# sch_camera.net
KiCad netlist of a schematic drawn in Altium Designer
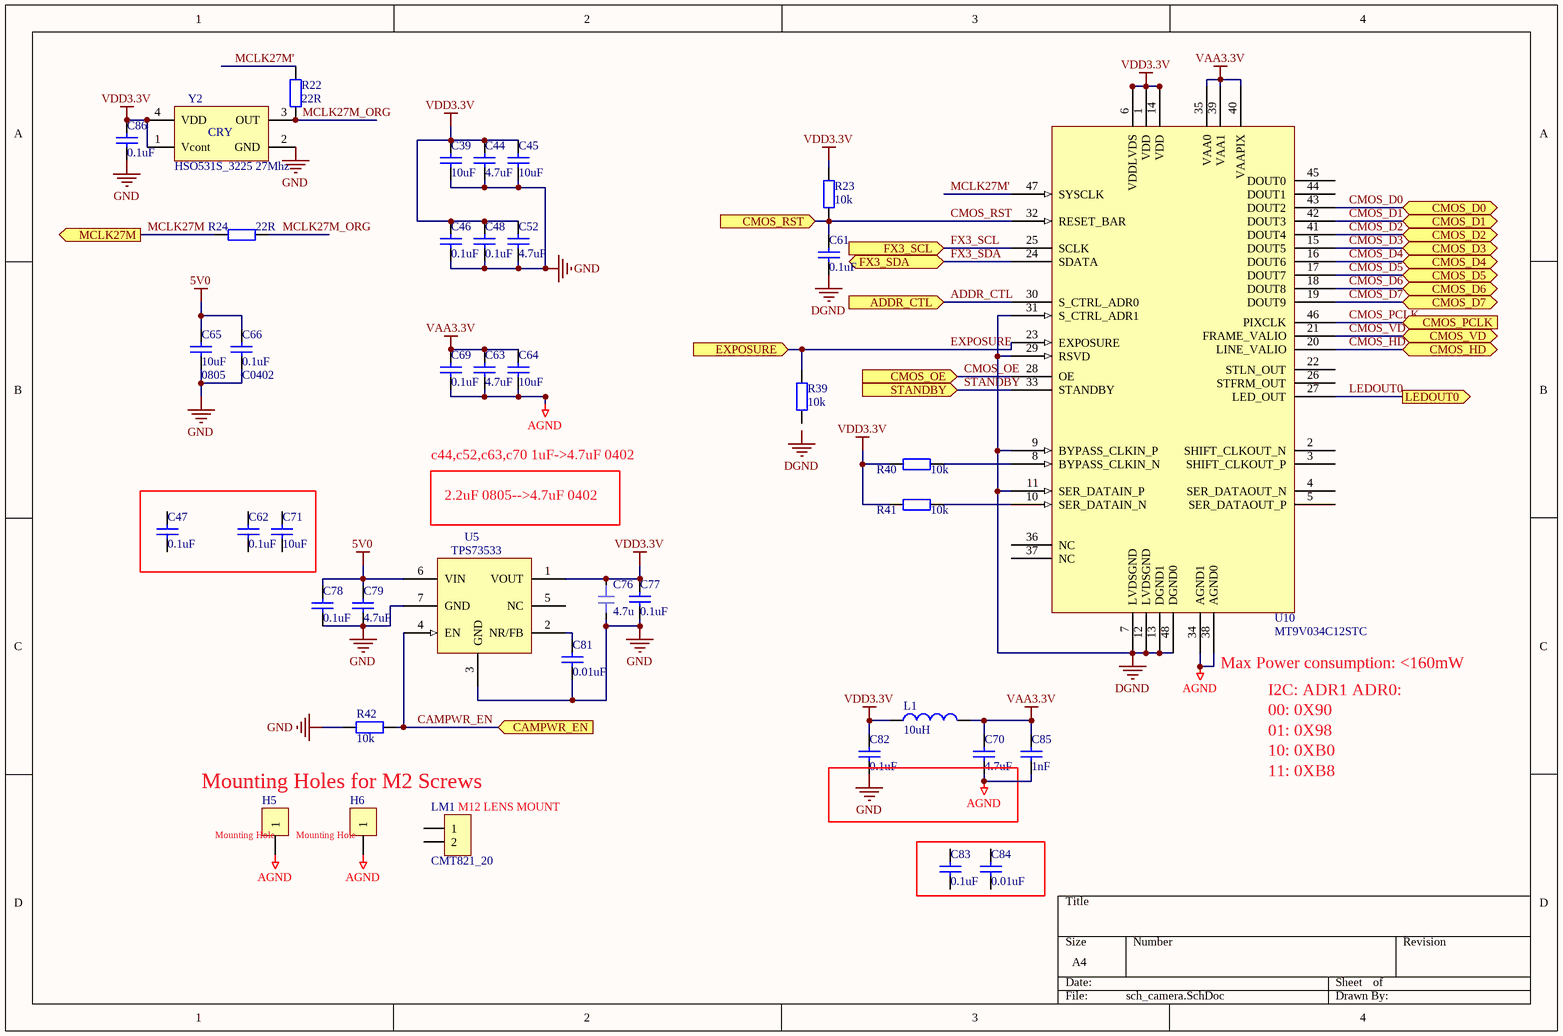
[diagram p0: sch_camera.SchDoc]

(export (version "E")
  (design (tool "Eeschema 10.0.6"))
  (components
    (comp (ref "C39")
      (value "10uF")
      (footprint "0805C")
      (description "Capacitor")
      (fields (field (name "PUBLISHER") "Altium Limited"))
      (libsource (lib "Miscellaneous Devices") (part "Cap"))
    )
    (comp (ref "C44")
      (value "4.7uF")
      (footprint "0402C")
      (description "Capacitor")
      (fields (field (name "PUBLISHER") "Altium Limited"))
      (libsource (lib "Miscellaneous Devices") (part "Cap"))
    )
    (comp (ref "C45")
      (value "10uF")
      (footprint "0805C")
      (description "Capacitor")
      (fields (field (name "PUBLISHER") "Altium Limited"))
      (libsource (lib "Miscellaneous Devices") (part "Cap"))
    )
    (comp (ref "C46")
      (value "0.1uF")
      (footprint "0402C")
      (description "Capacitor")
      (fields (field (name "PUBLISHER") "Altium Limited"))
      (libsource (lib "Miscellaneous Devices") (part "Cap"))
    )
    (comp (ref "C47")
      (value "0.1uF")
      (footprint "0402C")
      (description "Capacitor")
      (fields (field (name "PUBLISHER") "Altium Limited"))
      (libsource (lib "Miscellaneous Devices") (part "Cap"))
    )
    (comp (ref "C48")
      (value "0.1uF")
      (footprint "0402C")
      (description "Capacitor")
      (fields (field (name "PUBLISHER") "Altium Limited"))
      (libsource (lib "Miscellaneous Devices") (part "Cap"))
    )
    (comp (ref "C52")
      (value "4.7uF")
      (footprint "0402C")
      (description "Capacitor")
      (fields (field (name "PUBLISHER") "Altium Limited"))
      (libsource (lib "Miscellaneous Devices") (part "Cap"))
    )
    (comp (ref "C61")
      (value "0.1uF")
      (footprint "0402C")
      (description "Capacitor")
      (fields (field (name "PUBLISHER") "Altium Limited"))
      (libsource (lib "Miscellaneous Devices") (part "Cap"))
    )
    (comp (ref "C62")
      (value "0.1uF")
      (footprint "0402C")
      (description "Capacitor")
      (fields (field (name "PUBLISHER") "Altium Limited"))
      (libsource (lib "Miscellaneous Devices") (part "Cap"))
    )
    (comp (ref "C63")
      (value "4.7uF")
      (footprint "0402C")
      (description "Capacitor")
      (fields (field (name "PUBLISHER") "Altium Limited"))
      (libsource (lib "Miscellaneous Devices") (part "Cap"))
    )
    (comp (ref "C64")
      (value "10uF")
      (footprint "0805C")
      (description "Capacitor")
      (fields (field (name "PUBLISHER") "Altium Limited"))
      (libsource (lib "Miscellaneous Devices") (part "Cap"))
    )
    (comp (ref "C65")
      (value "10uF")
      (footprint "0805C")
      (description "Capacitor")
      (fields (field (name "ALTIUM_VALUE") "0805") (field (name "PUBLISHER") "Altium Limited"))
      (libsource (lib "Miscellaneous Devices") (part "Cap"))
    )
    (comp (ref "C66")
      (value "0.1uF")
      (footprint "0402C")
      (description "Capacitor")
      (fields (field (name "ALTIUM_VALUE") "C0402") (field (name "PUBLISHER") "Altium Limited"))
      (libsource (lib "Miscellaneous Devices") (part "Cap"))
    )
    (comp (ref "C69")
      (value "0.1uF")
      (footprint "0402C")
      (description "Capacitor")
      (fields (field (name "PUBLISHER") "Altium Limited"))
      (libsource (lib "Miscellaneous Devices") (part "Cap"))
    )
    (comp (ref "C70")
      (value "4.7uF")
      (footprint "0402C")
      (description "Capacitor")
      (fields (field (name "PUBLISHER") "Altium Limited"))
      (libsource (lib "Miscellaneous Devices") (part "Cap"))
    )
    (comp (ref "C71")
      (value "10uF")
      (footprint "0805C")
      (description "Capacitor")
      (fields (field (name "PUBLISHER") "Altium Limited"))
      (libsource (lib "Miscellaneous Devices") (part "Cap"))
    )
    (comp (ref "C76")
      (value "4.7u")
      (footprint "0402C_L")
      (description "CC0402MRX5R5BB475")
      (libsource (lib "V0P1") (part "cap0402"))
    )
    (comp (ref "C77")
      (value "0.1uF")
      (footprint "0402C_L")
      (description "Capacitor")
      (fields (field (name "PUBLISHER") "Altium Limited"))
      (libsource (lib "Miscellaneous Devices") (part "Cap"))
    )
    (comp (ref "C78")
      (value "0.1uF")
      (footprint "0402C")
      (description "Capacitor")
      (fields (field (name "PUBLISHER") "Altium Limited"))
      (libsource (lib "Miscellaneous Devices") (part "Cap"))
    )
    (comp (ref "C79")
      (value "4.7uF")
      (footprint "0402C_L")
      (description "Capacitor")
      (fields (field (name "Comment") "1uF") (field (name "PUBLISHER") "Altium Limited"))
      (libsource (lib "Miscellaneous Devices") (part "Cap"))
    )
    (comp (ref "C81")
      (value "0.01uF")
      (footprint "0402C_L")
      (description "Capacitor")
      (fields (field (name "PUBLISHER") "Altium Limited"))
      (libsource (lib "Miscellaneous Devices") (part "Cap"))
    )
    (comp (ref "C82")
      (value "0.1uF")
      (footprint "0402C_L")
      (description "Capacitor")
      (fields (field (name "PUBLISHER") "Altium Limited"))
      (libsource (lib "Miscellaneous Devices") (part "Cap"))
    )
    (comp (ref "C83")
      (value "0.1uF")
      (footprint "0402C_L")
      (description "Capacitor")
      (fields (field (name "PUBLISHER") "Altium Limited"))
      (libsource (lib "Miscellaneous Devices") (part "Cap"))
    )
    (comp (ref "C84")
      (value "0.01uF")
      (footprint "0402C_L")
      (description "Capacitor")
      (fields (field (name "PUBLISHER") "Altium Limited"))
      (libsource (lib "Miscellaneous Devices") (part "Cap"))
    )
    (comp (ref "C85")
      (value "1nF")
      (footprint "0402C_L")
      (description "Capacitor")
      (fields (field (name "PUBLISHER") "Altium Limited"))
      (libsource (lib "Miscellaneous Devices") (part "Cap"))
    )
    (comp (ref "C86")
      (value "0.1uF")
      (footprint "0402C_L")
      (description "Capacitor")
      (fields (field (name "PUBLISHER") "Altium Limited"))
      (libsource (lib "Miscellaneous Devices") (part "Cap"))
    )
    (comp (ref "H5")
      (value "CON1")
      (footprint "PAD_M3_D350_450")
      (description "Connector")
      (libsource (lib "SuperSchLib") (part "CON1"))
    )
    (comp (ref "H6")
      (value "CON1")
      (footprint "PAD_M3_D350_450")
      (description "Connector")
      (libsource (lib "SuperSchLib") (part "CON1"))
    )
    (comp (ref "L1")
      (value "10uH")
      (footprint "0805R")
      (description "Inductor")
      (libsource (lib "SWUST_ROBOT") (part "Inductor"))
    )
    (comp (ref "LM1")
      (value "CMT821_20")
      (footprint "PAD_M3_D350_450")
      (description "Connector")
      (libsource (lib "SuperSchLib") (part "CON2"))
    )
    (comp (ref "R22")
      (value "22R")
      (footprint "0402R_L")
      (description "Resistor")
      (fields (field (name "Comment") "0R") (field (name "PUBLISHER") "Altium Limited"))
      (libsource (lib "") (part "Resistor_1"))
    )
    (comp (ref "R23")
      (value "10k")
      (footprint "0402R")
      (description "Resistor")
      (fields (field (name "Comment") "10K") (field (name "PUBLISHER") "Altium Limited"))
      (libsource (lib "") (part "Resistor_3"))
    )
    (comp (ref "R24")
      (value "22R")
      (footprint "0402R")
      (description "Resistor")
      (fields (field (name "PUBLISHER") "Altium Limited"))
      (libsource (lib "") (part "Resistor_2"))
    )
    (comp (ref "R39")
      (value "10k")
      (footprint "0402R")
      (description "Resistor")
      (fields (field (name "Comment") "10K") (field (name "PUBLISHER") "Altium Limited"))
      (libsource (lib "") (part "Resistor_1"))
    )
    (comp (ref "R40")
      (value "10k")
      (footprint "0402R")
      (description "Resistor")
      (fields (field (name "Comment") "10K") (field (name "PUBLISHER") "Altium Limited"))
      (libsource (lib "SZG") (part "Resistor"))
    )
    (comp (ref "R41")
      (value "10k")
      (footprint "0402R")
      (description "Resistor")
      (fields (field (name "Comment") "10K") (field (name "PUBLISHER") "Altium Limited"))
      (libsource (lib "SZG") (part "Resistor"))
    )
    (comp (ref "R42")
      (value "10k")
      (footprint "0402R_L")
      (description "Resistor")
      (fields (field (name "Comment") "10K") (field (name "PUBLISHER") "Altium Limited"))
      (libsource (lib "SZG") (part "Resistor"))
    )
    (comp (ref "U5")
      (value "TPS73533")
      (footprint "SON6_P65L21W21H8_DRV")
      (libsource (lib "SZG") (part "TPS73533"))
    )
    (comp (ref "U10")
      (value "MT9V034C12STC")
      (footprint "CLCC48_P80L114W114H23")
      (libsource (lib "TXW") (part "MT9V034"))
    )
    (comp (ref "Y2")
      (value "HSO531S_3225 27Mhz")
      (footprint "XTAL_3225")
      (description "有源晶振")
      (libsource (lib "超集元件库") (part "CRY"))
    )
  )
  (nets
    (net (code "1") (name "/ADDR_CTL") (class "Default")
      (node (ref "U10") (pin "30") (pinfunction "S_CTRL_ADR0_30") (pintype "passive"))
    )
    (net (code "2") (name "/CAMPWR_EN") (class "Default")
      (node (ref "R42") (pin "1") (pinfunction "1_1") (pintype "passive"))
      (node (ref "U5") (pin "4") (pinfunction "EN_4") (pintype "input"))
    )
    (net (code "3") (name "/CMOS_D0") (class "Default")
      (node (ref "U10") (pin "43") (pinfunction "DOUT2_43") (pintype "passive"))
    )
    (net (code "4") (name "/CMOS_D1") (class "Default")
      (node (ref "U10") (pin "42") (pinfunction "DOUT3_42") (pintype "passive"))
    )
    (net (code "5") (name "/CMOS_D2") (class "Default")
      (node (ref "U10") (pin "41") (pinfunction "DOUT4_41") (pintype "passive"))
    )
    (net (code "6") (name "/CMOS_D3") (class "Default")
      (node (ref "U10") (pin "15") (pinfunction "DOUT5_15") (pintype "passive"))
    )
    (net (code "7") (name "/CMOS_D4") (class "Default")
      (node (ref "U10") (pin "16") (pinfunction "DOUT6_16") (pintype "passive"))
    )
    (net (code "8") (name "/CMOS_D5") (class "Default")
      (node (ref "U10") (pin "17") (pinfunction "DOUT7_17") (pintype "passive"))
    )
    (net (code "9") (name "/CMOS_D6") (class "Default")
      (node (ref "U10") (pin "18") (pinfunction "DOUT8_18") (pintype "passive"))
    )
    (net (code "10") (name "/CMOS_D7") (class "Default")
      (node (ref "U10") (pin "19") (pinfunction "DOUT9_19") (pintype "passive"))
    )
    (net (code "11") (name "/CMOS_HD") (class "Default")
      (node (ref "U10") (pin "20") (pinfunction "LINE_VALIO_20") (pintype "passive"))
    )
    (net (code "12") (name "/CMOS_OE") (class "Default")
      (node (ref "U10") (pin "28") (pinfunction "OE_28") (pintype "passive"))
    )
    (net (code "13") (name "/CMOS_PCLK") (class "Default")
      (node (ref "U10") (pin "46") (pinfunction "PIXCLK_46") (pintype "passive"))
    )
    (net (code "14") (name "/CMOS_RST") (class "Default")
      (node (ref "C61") (pin "2") (pinfunction "2_2") (pintype "passive"))
      (node (ref "R23") (pin "1") (pinfunction "1_1") (pintype "passive"))
      (node (ref "U10") (pin "32") (pinfunction "RESET_BAR_32") (pintype "input"))
    )
    (net (code "15") (name "/CMOS_VD") (class "Default")
      (node (ref "U10") (pin "21") (pinfunction "FRAME_VALIO_21") (pintype "passive"))
    )
    (net (code "16") (name "/EXPOSURE") (class "Default")
      (node (ref "R39") (pin "1") (pinfunction "1_1") (pintype "passive"))
      (node (ref "U10") (pin "23") (pinfunction "EXPOSURE_23") (pintype "input"))
    )
    (net (code "17") (name "/FX3_SCL") (class "Default")
      (node (ref "U10") (pin "25") (pinfunction "SCLK_25") (pintype "passive"))
    )
    (net (code "18") (name "/FX3_SDA") (class "Default")
      (node (ref "U10") (pin "24") (pinfunction "SDATA_24") (pintype "passive"))
    )
    (net (code "19") (name "/LEDOUT0") (class "Default")
      (node (ref "U10") (pin "27") (pinfunction "LED_OUT_27") (pintype "passive"))
    )
    (net (code "20") (name "/MCLK27M") (class "Default")
      (node (ref "R24") (pin "1") (pinfunction "1_1") (pintype "passive"))
    )
    (net (code "21") (name "/MCLK27M'") (class "Default")
      (node (ref "R22") (pin "1") (pinfunction "1_1") (pintype "passive"))
      (node (ref "U10") (pin "47") (pinfunction "SYSCLK_47") (pintype "input"))
    )
    (net (code "22") (name "/MCLK27M_ORG") (class "Default")
      (node (ref "R22") (pin "2") (pinfunction "2_2") (pintype "passive"))
      (node (ref "R24") (pin "2") (pinfunction "2_2") (pintype "passive"))
      (node (ref "Y2") (pin "3") (pinfunction "OUT_3") (pintype "passive"))
    )
    (net (code "23") (name "/STANDBY") (class "Default")
      (node (ref "U10") (pin "33") (pinfunction "STANDBY_33") (pintype "passive"))
    )
    (net (code "24") (name "5V0") (class "Default")
      (node (ref "C65") (pin "2") (pinfunction "2_2") (pintype "passive"))
      (node (ref "C66") (pin "2") (pinfunction "2_2") (pintype "passive"))
      (node (ref "C78") (pin "2") (pinfunction "2_2") (pintype "passive"))
      (node (ref "C79") (pin "2") (pinfunction "2_2") (pintype "passive"))
      (node (ref "U5") (pin "6") (pinfunction "VIN_6") (pintype "passive"))
    )
    (net (code "25") (name "AGND") (class "Default")
      (node (ref "C63") (pin "1") (pinfunction "1_1") (pintype "passive"))
      (node (ref "C64") (pin "1") (pinfunction "1_1") (pintype "passive"))
      (node (ref "C69") (pin "1") (pinfunction "1_1") (pintype "passive"))
      (node (ref "C70") (pin "1") (pinfunction "1_1") (pintype "passive"))
      (node (ref "C85") (pin "1") (pinfunction "1_1") (pintype "passive"))
      (node (ref "H5") (pin "1") (pinfunction "1_1") (pintype "passive"))
      (node (ref "H6") (pin "1") (pinfunction "1_1") (pintype "passive"))
      (node (ref "U10") (pin "34") (pinfunction "AGND1_34") (pintype "power_in"))
      (node (ref "U10") (pin "38") (pinfunction "AGND0_38") (pintype "power_in"))
    )
    (net (code "26") (name "DGND") (class "Default")
      (node (ref "C61") (pin "1") (pinfunction "1_1") (pintype "passive"))
      (node (ref "U10") (pin "11") (pinfunction "SER_DATAIN_P_11") (pintype "input"))
      (node (ref "U10") (pin "12") (pinfunction "LVDSGND_12") (pintype "power_in"))
      (node (ref "U10") (pin "13") (pinfunction "DGND1_13") (pintype "power_in"))
      (node (ref "U10") (pin "29") (pinfunction "RSVD_29") (pintype "input"))
      (node (ref "U10") (pin "31") (pinfunction "S_CTRL_ADR1_31") (pintype "input"))
      (node (ref "U10") (pin "48") (pinfunction "DGND0_48") (pintype "power_in"))
      (node (ref "U10") (pin "7") (pinfunction "LVDSGND_7") (pintype "power_in"))
      (node (ref "U10") (pin "9") (pinfunction "BYPASS_CLKIN_P_9") (pintype "input"))
    )
    (net (code "27") (name "GND") (class "Default")
      (node (ref "C39") (pin "1") (pinfunction "1_1") (pintype "passive"))
      (node (ref "C44") (pin "1") (pinfunction "1_1") (pintype "passive"))
      (node (ref "C45") (pin "1") (pinfunction "1_1") (pintype "passive"))
      (node (ref "C46") (pin "1") (pinfunction "1_1") (pintype "passive"))
      (node (ref "C48") (pin "1") (pinfunction "1_1") (pintype "passive"))
      (node (ref "C52") (pin "1") (pinfunction "1_1") (pintype "passive"))
      (node (ref "C65") (pin "1") (pinfunction "1_1") (pintype "passive"))
      (node (ref "C66") (pin "1") (pinfunction "1_1") (pintype "passive"))
      (node (ref "C76") (pin "2") (pinfunction "2_2") (pintype "passive"))
      (node (ref "C77") (pin "1") (pinfunction "1_1") (pintype "passive"))
      (node (ref "C78") (pin "1") (pinfunction "1_1") (pintype "passive"))
      (node (ref "C79") (pin "1") (pinfunction "1_1") (pintype "passive"))
      (node (ref "C81") (pin "1") (pinfunction "1_1") (pintype "passive"))
      (node (ref "C82") (pin "1") (pinfunction "1_1") (pintype "passive"))
      (node (ref "C86") (pin "1") (pinfunction "1_1") (pintype "passive"))
      (node (ref "R42") (pin "2") (pinfunction "2_2") (pintype "passive"))
      (node (ref "U5") (pin "3") (pinfunction "GND_3") (pintype "passive"))
      (node (ref "U5") (pin "7") (pinfunction "GND_7") (pintype "passive"))
      (node (ref "Y2") (pin "2") (pinfunction "GND_2") (pintype "passive"))
    )
    (net (code "28") (name "Net-(U5-NR{slash}FB)") (class "Default")
      (node (ref "C81") (pin "2") (pinfunction "2_2") (pintype "passive"))
      (node (ref "U5") (pin "2") (pinfunction "NR/FB_2") (pintype "passive"))
    )
    (net (code "29") (name "Net-(U10-BYPASS_CLKIN_N)") (class "Default")
      (node (ref "R40") (pin "1") (pinfunction "1_1") (pintype "passive"))
      (node (ref "U10") (pin "8") (pinfunction "BYPASS_CLKIN_N_8") (pintype "input"))
    )
    (net (code "30") (name "Net-(U10-SER_DATAIN_N)") (class "Default")
      (node (ref "R41") (pin "1") (pinfunction "1_1") (pintype "passive"))
      (node (ref "U10") (pin "10") (pinfunction "SER_DATAIN_N_10") (pintype "input"))
    )
    (net (code "31") (name "VAA3.3V") (class "Default")
      (node (ref "C63") (pin "2") (pinfunction "2_2") (pintype "passive"))
      (node (ref "C64") (pin "2") (pinfunction "2_2") (pintype "passive"))
      (node (ref "C69") (pin "2") (pinfunction "2_2") (pintype "passive"))
      (node (ref "C70") (pin "2") (pinfunction "2_2") (pintype "passive"))
      (node (ref "C85") (pin "2") (pinfunction "2_2") (pintype "passive"))
      (node (ref "L1") (pin "2") (pinfunction "2_2") (pintype "passive"))
      (node (ref "U10") (pin "35") (pinfunction "VAA0_35") (pintype "power_in"))
      (node (ref "U10") (pin "39") (pinfunction "VAA1_39") (pintype "power_in"))
      (node (ref "U10") (pin "40") (pinfunction "VAAPIX_40") (pintype "power_in"))
    )
    (net (code "32") (name "VDD3.3V") (class "Default")
      (node (ref "C39") (pin "2") (pinfunction "2_2") (pintype "passive"))
      (node (ref "C44") (pin "2") (pinfunction "2_2") (pintype "passive"))
      (node (ref "C45") (pin "2") (pinfunction "2_2") (pintype "passive"))
      (node (ref "C46") (pin "2") (pinfunction "2_2") (pintype "passive"))
      (node (ref "C48") (pin "2") (pinfunction "2_2") (pintype "passive"))
      (node (ref "C52") (pin "2") (pinfunction "2_2") (pintype "passive"))
      (node (ref "C76") (pin "1") (pinfunction "1_1") (pintype "passive"))
      (node (ref "C77") (pin "2") (pinfunction "2_2") (pintype "passive"))
      (node (ref "C82") (pin "2") (pinfunction "2_2") (pintype "passive"))
      (node (ref "C86") (pin "2") (pinfunction "2_2") (pintype "passive"))
      (node (ref "L1") (pin "1") (pinfunction "1_1") (pintype "passive"))
      (node (ref "R23") (pin "2") (pinfunction "2_2") (pintype "passive"))
      (node (ref "R40") (pin "2") (pinfunction "2_2") (pintype "passive"))
      (node (ref "R41") (pin "2") (pinfunction "2_2") (pintype "passive"))
      (node (ref "U10") (pin "1") (pinfunction "VDD_1") (pintype "power_in"))
      (node (ref "U10") (pin "14") (pinfunction "VDD_14") (pintype "power_in"))
      (node (ref "U10") (pin "6") (pinfunction "VDDLVDS_6") (pintype "power_in"))
      (node (ref "U5") (pin "1") (pinfunction "VOUT_1") (pintype "passive"))
      (node (ref "Y2") (pin "1") (pinfunction "Vcont_1") (pintype "passive"))
      (node (ref "Y2") (pin "4") (pinfunction "VDD_4") (pintype "passive"))
    )
    (net (code "33") (name "unconnected-(C47-Pad1)") (class "Default")
      (node (ref "C47") (pin "1") (pinfunction "1_1") (pintype "passive"))
    )
    (net (code "34") (name "unconnected-(C47-Pad2)") (class "Default")
      (node (ref "C47") (pin "2") (pinfunction "2_2") (pintype "passive"))
    )
    (net (code "35") (name "unconnected-(C62-Pad1)") (class "Default")
      (node (ref "C62") (pin "1") (pinfunction "1_1") (pintype "passive"))
    )
    (net (code "36") (name "unconnected-(C62-Pad2)") (class "Default")
      (node (ref "C62") (pin "2") (pinfunction "2_2") (pintype "passive"))
    )
    (net (code "37") (name "unconnected-(C71-Pad1)") (class "Default")
      (node (ref "C71") (pin "1") (pinfunction "1_1") (pintype "passive"))
    )
    (net (code "38") (name "unconnected-(C71-Pad2)") (class "Default")
      (node (ref "C71") (pin "2") (pinfunction "2_2") (pintype "passive"))
    )
    (net (code "39") (name "unconnected-(C83-Pad1)") (class "Default")
      (node (ref "C83") (pin "1") (pinfunction "1_1") (pintype "passive"))
    )
    (net (code "40") (name "unconnected-(C83-Pad2)") (class "Default")
      (node (ref "C83") (pin "2") (pinfunction "2_2") (pintype "passive"))
    )
    (net (code "41") (name "unconnected-(C84-Pad1)") (class "Default")
      (node (ref "C84") (pin "1") (pinfunction "1_1") (pintype "passive"))
    )
    (net (code "42") (name "unconnected-(C84-Pad2)") (class "Default")
      (node (ref "C84") (pin "2") (pinfunction "2_2") (pintype "passive"))
    )
    (net (code "43") (name "unconnected-(LM1-Pad1)") (class "Default")
      (node (ref "LM1") (pin "1") (pinfunction "1_1") (pintype "passive"))
    )
    (net (code "44") (name "unconnected-(LM1-Pad2)") (class "Default")
      (node (ref "LM1") (pin "2") (pinfunction "2_2") (pintype "passive"))
    )
    (net (code "45") (name "unconnected-(R39-Pad2)") (class "Default")
      (node (ref "R39") (pin "2") (pinfunction "2_2") (pintype "passive"))
    )
    (net (code "46") (name "unconnected-(U5-NC-Pad5)") (class "Default")
      (node (ref "U5") (pin "5") (pinfunction "NC_5") (pintype "passive"))
    )
    (net (code "47") (name "unconnected-(U10-DOUT0-Pad45)") (class "Default")
      (node (ref "U10") (pin "45") (pinfunction "DOUT0_45") (pintype "passive"))
    )
    (net (code "48") (name "unconnected-(U10-DOUT1-Pad44)") (class "Default")
      (node (ref "U10") (pin "44") (pinfunction "DOUT1_44") (pintype "passive"))
    )
    (net (code "49") (name "unconnected-(U10-NC-Pad36)") (class "Default")
      (node (ref "U10") (pin "36") (pinfunction "NC_36") (pintype "passive"))
    )
    (net (code "50") (name "unconnected-(U10-NC-Pad37)") (class "Default")
      (node (ref "U10") (pin "37") (pinfunction "NC_37") (pintype "power_in"))
    )
    (net (code "51") (name "unconnected-(U10-SER_DATAOUT_N-Pad4)") (class "Default")
      (node (ref "U10") (pin "4") (pinfunction "SER_DATAOUT_N_4") (pintype "passive"))
    )
    (net (code "52") (name "unconnected-(U10-SER_DATAOUT_P-Pad5)") (class "Default")
      (node (ref "U10") (pin "5") (pinfunction "SER_DATAOUT_P_5") (pintype "passive"))
    )
    (net (code "53") (name "unconnected-(U10-SHIFT_CLKOUT_N-Pad2)") (class "Default")
      (node (ref "U10") (pin "2") (pinfunction "SHIFT_CLKOUT_N_2") (pintype "passive"))
    )
    (net (code "54") (name "unconnected-(U10-SHIFT_CLKOUT_P-Pad3)") (class "Default")
      (node (ref "U10") (pin "3") (pinfunction "SHIFT_CLKOUT_P_3") (pintype "passive"))
    )
    (net (code "55") (name "unconnected-(U10-STFRM_OUT-Pad26)") (class "Default")
      (node (ref "U10") (pin "26") (pinfunction "STFRM_OUT_26") (pintype "passive"))
    )
    (net (code "56") (name "unconnected-(U10-STLN_OUT-Pad22)") (class "Default")
      (node (ref "U10") (pin "22") (pinfunction "STLN_OUT_22") (pintype "passive"))
    )
  )
)
